# untitled.net
KiCad netlist of a schematic drawn in EAGLE
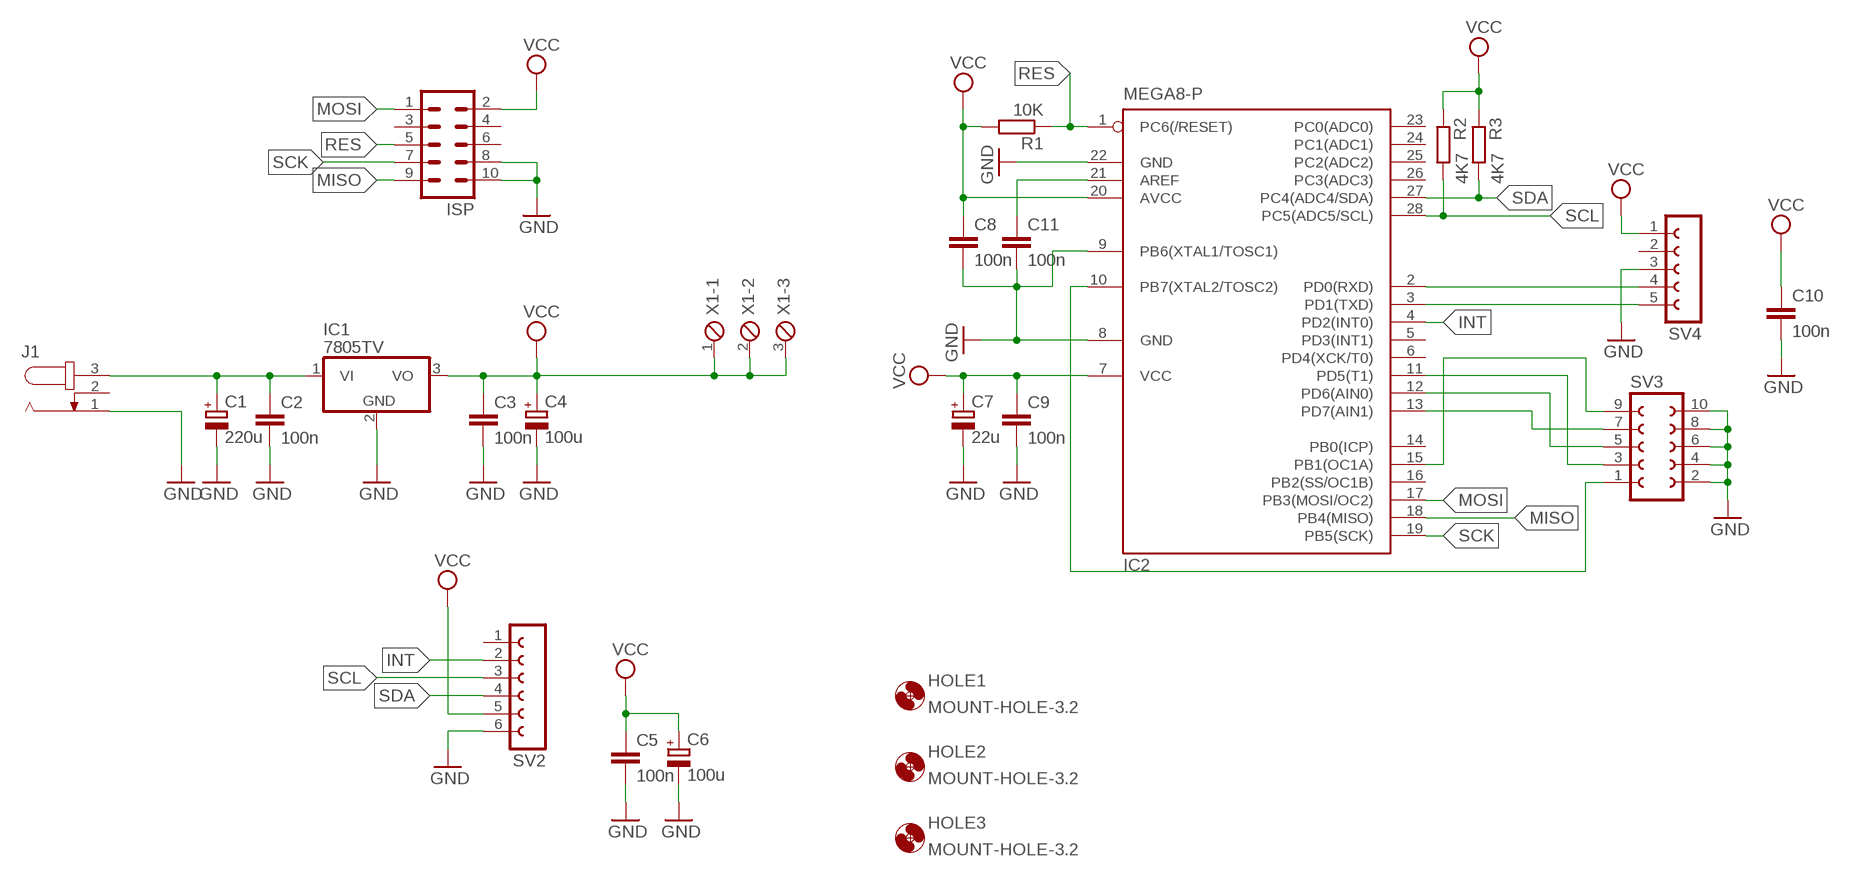
[diagram p0: schematic, sheet 1]

(export (version "E")
  (design (tool "Eeschema 10.0.6"))
  (components
    (comp (ref "C1")
      (value "220u")
      (footprint "eagle-import:E3,5-8")
      (libsource (lib "eagle-import") (part "CPOL-EUE3.5-8"))
    )
    (comp (ref "C2")
      (value "100n")
      (footprint "eagle-import:C025-025X050")
      (libsource (lib "eagle-import") (part "C-EU025-025X050"))
    )
    (comp (ref "C3")
      (value "100n")
      (footprint "eagle-import:C025-025X050")
      (libsource (lib "eagle-import") (part "C-EU025-025X050"))
    )
    (comp (ref "C4")
      (value "100u")
      (footprint "eagle-import:E2,5-5")
      (libsource (lib "eagle-import") (part "CPOL-EUE2.5-5"))
    )
    (comp (ref "C5")
      (value "100n")
      (footprint "eagle-import:C025-025X050")
      (libsource (lib "eagle-import") (part "C-EU025-025X050"))
    )
    (comp (ref "C6")
      (value "100u")
      (footprint "eagle-import:E2,5-5")
      (libsource (lib "eagle-import") (part "CPOL-EUE2.5-5"))
    )
    (comp (ref "C7")
      (value "22u")
      (footprint "eagle-import:E2,5-5")
      (libsource (lib "eagle-import") (part "CPOL-EUE2.5-5"))
    )
    (comp (ref "C8")
      (value "100n")
      (footprint "eagle-import:C025-025X050")
      (libsource (lib "eagle-import") (part "C-EU025-025X050"))
    )
    (comp (ref "C9")
      (value "100n")
      (footprint "eagle-import:C025-030X050")
      (libsource (lib "eagle-import") (part "C-EU025-030X050"))
    )
    (comp (ref "C10")
      (value "100n")
      (footprint "eagle-import:C025-025X050")
      (libsource (lib "eagle-import") (part "C-EU025-025X050"))
    )
    (comp (ref "C11")
      (value "100n")
      (footprint "eagle-import:C025-025X050")
      (libsource (lib "eagle-import") (part "C-EU025-025X050"))
    )
    (comp (ref "HOLE1")
      (value "MOUNT-HOLE-3.2")
      (footprint "eagle-import:3,2")
      (libsource (lib "eagle-import") (part "MOUNT-HOLE-3.2"))
    )
    (comp (ref "HOLE2")
      (value "MOUNT-HOLE-3.2")
      (footprint "eagle-import:3,2")
      (libsource (lib "eagle-import") (part "MOUNT-HOLE-3.2"))
    )
    (comp (ref "HOLE3")
      (value "MOUNT-HOLE-3.2")
      (footprint "eagle-import:3,2")
      (libsource (lib "eagle-import") (part "MOUNT-HOLE-3.2"))
    )
    (comp (ref "IC1")
      (value "7805TV")
      (footprint "eagle-import:TO220V")
      (libsource (lib "eagle-import") (part "78TV05"))
    )
    (comp (ref "IC2")
      (value "MEGA8-P")
      (footprint "eagle-import:DIL28-3")
      (libsource (lib "eagle-import") (part "MEGA8-P"))
    )
    (comp (ref "ISP")
      (value "ML10")
      (footprint "eagle-import:ML10")
      (libsource (lib "eagle-import") (part "ML10"))
    )
    (comp (ref "J1")
      (value "JACK-PLUG1")
      (footprint "eagle-import:SPC4078")
      (libsource (lib "eagle-import") (part "JACK-PLUG1"))
    )
    (comp (ref "R1")
      (value "10K")
      (footprint "eagle-import:0204_7")
      (libsource (lib "eagle-import") (part "R-EU_0204/7"))
    )
    (comp (ref "R2")
      (value "4K7")
      (footprint "eagle-import:0204_7")
      (libsource (lib "eagle-import") (part "R-EU_0204/7"))
    )
    (comp (ref "R3")
      (value "4K7")
      (footprint "eagle-import:0204_7")
      (libsource (lib "eagle-import") (part "R-EU_0204/7"))
    )
    (comp (ref "SV2")
      (value "FE06-1")
      (footprint "eagle-import:FE06")
      (libsource (lib "eagle-import") (part "FE06-1"))
    )
    (comp (ref "SV3")
      (value "FE05-2")
      (footprint "eagle-import:FE05-2")
      (libsource (lib "eagle-import") (part "FE05-2"))
    )
    (comp (ref "SV4")
      (value "FE05-1")
      (footprint "eagle-import:FE05-1")
      (libsource (lib "eagle-import") (part "FE05-1"))
    )
    (comp (ref "X1")
      (value "MPT3")
      (footprint "eagle-import:3POL254")
      (libsource (lib "eagle-import") (part "MPT3"))
    )
  )
  (nets
    (net (code "1") (name "GND") (class "Default")
      (node (ref "C1") (pin "-") (pinfunction "-_-") (pintype "passive"))
      (node (ref "C10") (pin "2") (pinfunction "2_2") (pintype "passive"))
      (node (ref "C11") (pin "2") (pinfunction "2_2") (pintype "passive"))
      (node (ref "C2") (pin "2") (pinfunction "2_2") (pintype "passive"))
      (node (ref "C3") (pin "2") (pinfunction "2_2") (pintype "passive"))
      (node (ref "C4") (pin "-") (pinfunction "-_-") (pintype "passive"))
      (node (ref "C5") (pin "2") (pinfunction "2_2") (pintype "passive"))
      (node (ref "C6") (pin "-") (pinfunction "-_-") (pintype "passive"))
      (node (ref "C7") (pin "-") (pinfunction "-_-") (pintype "passive"))
      (node (ref "C8") (pin "2") (pinfunction "2_2") (pintype "passive"))
      (node (ref "C9") (pin "2") (pinfunction "2_2") (pintype "passive"))
      (node (ref "IC1") (pin "2") (pinfunction "GND_2") (pintype "passive"))
      (node (ref "IC2") (pin "22") (pinfunction "GND_22") (pintype "power_in"))
      (node (ref "IC2") (pin "8") (pinfunction "GND_8") (pintype "power_in"))
      (node (ref "IC2") (pin "9") (pinfunction "PB6(XTAL1/TOSC1)_9") (pintype "bidirectional"))
      (node (ref "ISP") (pin "10") (pinfunction "10_10") (pintype "passive"))
      (node (ref "ISP") (pin "8") (pinfunction "8_8") (pintype "passive"))
      (node (ref "J1") (pin "1") (pinfunction "1_1") (pintype "passive"))
      (node (ref "SV2") (pin "6") (pinfunction "6_6") (pintype "passive"))
      (node (ref "SV3") (pin "10") (pinfunction "10_10") (pintype "passive"))
      (node (ref "SV3") (pin "2") (pinfunction "2_2") (pintype "passive"))
      (node (ref "SV3") (pin "4") (pinfunction "4_4") (pintype "passive"))
      (node (ref "SV3") (pin "6") (pinfunction "6_6") (pintype "passive"))
      (node (ref "SV3") (pin "8") (pinfunction "8_8") (pintype "passive"))
      (node (ref "SV4") (pin "3") (pinfunction "3_3") (pintype "passive"))
    )
    (net (code "2") (name "INT") (class "Default")
      (node (ref "IC2") (pin "4") (pinfunction "PD2(INT0)_4") (pintype "bidirectional"))
      (node (ref "SV2") (pin "2") (pinfunction "2_2") (pintype "passive"))
    )
    (net (code "3") (name "MISO") (class "Default")
      (node (ref "IC2") (pin "18") (pinfunction "PB4(MISO)_18") (pintype "bidirectional"))
      (node (ref "ISP") (pin "9") (pinfunction "9_9") (pintype "passive"))
    )
    (net (code "4") (name "MOSI") (class "Default")
      (node (ref "IC2") (pin "17") (pinfunction "PB3(MOSI/OC2)_17") (pintype "bidirectional"))
      (node (ref "ISP") (pin "1") (pinfunction "1_1") (pintype "passive"))
    )
    (net (code "5") (name "Net-(IC1-VI)") (class "Default")
      (node (ref "C1") (pin "+") (pinfunction "+_+") (pintype "passive"))
      (node (ref "C2") (pin "1") (pinfunction "1_1") (pintype "passive"))
      (node (ref "IC1") (pin "1") (pinfunction "VI_1") (pintype "input"))
      (node (ref "J1") (pin "3") (pinfunction "3_3") (pintype "passive"))
    )
    (net (code "6") (name "Net-(IC2-AREF)") (class "Default")
      (node (ref "C11") (pin "1") (pinfunction "1_1") (pintype "passive"))
      (node (ref "IC2") (pin "21") (pinfunction "AREF_21") (pintype "passive"))
    )
    (net (code "7") (name "Net-(IC2-PB1(OC1A))") (class "Default")
      (node (ref "IC2") (pin "15") (pinfunction "PB1(OC1A)_15") (pintype "bidirectional"))
      (node (ref "SV3") (pin "9") (pinfunction "9_9") (pintype "passive"))
    )
    (net (code "8") (name "Net-(IC2-PB7(XTAL2{slash}TOSC2))") (class "Default")
      (node (ref "IC2") (pin "10") (pinfunction "PB7(XTAL2/TOSC2)_10") (pintype "bidirectional"))
      (node (ref "SV3") (pin "1") (pinfunction "1_1") (pintype "passive"))
    )
    (net (code "9") (name "Net-(IC2-PD0(RXD))") (class "Default")
      (node (ref "IC2") (pin "2") (pinfunction "PD0(RXD)_2") (pintype "bidirectional"))
      (node (ref "SV4") (pin "4") (pinfunction "4_4") (pintype "passive"))
    )
    (net (code "10") (name "Net-(IC2-PD1(TXD))") (class "Default")
      (node (ref "IC2") (pin "3") (pinfunction "PD1(TXD)_3") (pintype "bidirectional"))
      (node (ref "SV4") (pin "5") (pinfunction "5_5") (pintype "passive"))
    )
    (net (code "11") (name "Net-(IC2-PD5(T1))") (class "Default")
      (node (ref "IC2") (pin "11") (pinfunction "PD5(T1)_11") (pintype "bidirectional"))
      (node (ref "SV3") (pin "3") (pinfunction "3_3") (pintype "passive"))
    )
    (net (code "12") (name "Net-(IC2-PD6(AIN0))") (class "Default")
      (node (ref "IC2") (pin "12") (pinfunction "PD6(AIN0)_12") (pintype "bidirectional"))
      (node (ref "SV3") (pin "5") (pinfunction "5_5") (pintype "passive"))
    )
    (net (code "13") (name "Net-(IC2-PD7(AIN1))") (class "Default")
      (node (ref "IC2") (pin "13") (pinfunction "PD7(AIN1)_13") (pintype "bidirectional"))
      (node (ref "SV3") (pin "7") (pinfunction "7_7") (pintype "passive"))
    )
    (net (code "14") (name "RES") (class "Default")
      (node (ref "IC2") (pin "1") (pinfunction "PC6(/RESET)_1") (pintype "bidirectional"))
      (node (ref "ISP") (pin "5") (pinfunction "5_5") (pintype "passive"))
      (node (ref "R1") (pin "1") (pinfunction "1_1") (pintype "passive"))
    )
    (net (code "15") (name "SCK") (class "Default")
      (node (ref "IC2") (pin "19") (pinfunction "PB5(SCK)_19") (pintype "bidirectional"))
      (node (ref "ISP") (pin "7") (pinfunction "7_7") (pintype "passive"))
    )
    (net (code "16") (name "SCL") (class "Default")
      (node (ref "IC2") (pin "28") (pinfunction "PC5(ADC5/SCL)_28") (pintype "bidirectional"))
      (node (ref "R2") (pin "2") (pinfunction "2_2") (pintype "passive"))
      (node (ref "SV2") (pin "3") (pinfunction "3_3") (pintype "passive"))
    )
    (net (code "17") (name "SDA") (class "Default")
      (node (ref "IC2") (pin "27") (pinfunction "PC4(ADC4/SDA)_27") (pintype "bidirectional"))
      (node (ref "R3") (pin "2") (pinfunction "2_2") (pintype "passive"))
      (node (ref "SV2") (pin "4") (pinfunction "4_4") (pintype "passive"))
    )
    (net (code "18") (name "VCC") (class "Default")
      (node (ref "C10") (pin "1") (pinfunction "1_1") (pintype "passive"))
      (node (ref "C3") (pin "1") (pinfunction "1_1") (pintype "passive"))
      (node (ref "C4") (pin "+") (pinfunction "+_+") (pintype "passive"))
      (node (ref "C5") (pin "1") (pinfunction "1_1") (pintype "passive"))
      (node (ref "C6") (pin "+") (pinfunction "+_+") (pintype "passive"))
      (node (ref "C7") (pin "+") (pinfunction "+_+") (pintype "passive"))
      (node (ref "C8") (pin "1") (pinfunction "1_1") (pintype "passive"))
      (node (ref "C9") (pin "1") (pinfunction "1_1") (pintype "passive"))
      (node (ref "IC1") (pin "3") (pinfunction "VO_3") (pintype "passive"))
      (node (ref "IC2") (pin "20") (pinfunction "AVCC_20") (pintype "power_in"))
      (node (ref "IC2") (pin "7") (pinfunction "VCC_7") (pintype "power_in"))
      (node (ref "ISP") (pin "2") (pinfunction "2_2") (pintype "passive"))
      (node (ref "R1") (pin "2") (pinfunction "2_2") (pintype "passive"))
      (node (ref "R2") (pin "1") (pinfunction "1_1") (pintype "passive"))
      (node (ref "R3") (pin "1") (pinfunction "1_1") (pintype "passive"))
      (node (ref "SV2") (pin "5") (pinfunction "5_5") (pintype "passive"))
      (node (ref "SV4") (pin "1") (pinfunction "1_1") (pintype "passive"))
      (node (ref "X1") (pin "1") (pinfunction "1_1") (pintype "passive"))
      (node (ref "X1") (pin "2") (pinfunction "1_2") (pintype "passive"))
      (node (ref "X1") (pin "3") (pinfunction "1_3") (pintype "passive"))
    )
    (net (code "19") (name "unconnected-(IC2-PB0(ICP)-Pad14)") (class "Default")
      (node (ref "IC2") (pin "14") (pinfunction "PB0(ICP)_14") (pintype "bidirectional"))
    )
    (net (code "20") (name "unconnected-(IC2-PB2(SS{slash}OC1B)-Pad16)") (class "Default")
      (node (ref "IC2") (pin "16") (pinfunction "PB2(SS/OC1B)_16") (pintype "bidirectional"))
    )
    (net (code "21") (name "unconnected-(IC2-PC0(ADC0)-Pad23)") (class "Default")
      (node (ref "IC2") (pin "23") (pinfunction "PC0(ADC0)_23") (pintype "bidirectional"))
    )
    (net (code "22") (name "unconnected-(IC2-PC1(ADC1)-Pad24)") (class "Default")
      (node (ref "IC2") (pin "24") (pinfunction "PC1(ADC1)_24") (pintype "bidirectional"))
    )
    (net (code "23") (name "unconnected-(IC2-PC2(ADC2)-Pad25)") (class "Default")
      (node (ref "IC2") (pin "25") (pinfunction "PC2(ADC2)_25") (pintype "bidirectional"))
    )
    (net (code "24") (name "unconnected-(IC2-PC3(ADC3)-Pad26)") (class "Default")
      (node (ref "IC2") (pin "26") (pinfunction "PC3(ADC3)_26") (pintype "bidirectional"))
    )
    (net (code "25") (name "unconnected-(IC2-PD3(INT1)-Pad5)") (class "Default")
      (node (ref "IC2") (pin "5") (pinfunction "PD3(INT1)_5") (pintype "bidirectional"))
    )
    (net (code "26") (name "unconnected-(IC2-PD4(XCK{slash}T0)-Pad6)") (class "Default")
      (node (ref "IC2") (pin "6") (pinfunction "PD4(XCK/T0)_6") (pintype "bidirectional"))
    )
    (net (code "27") (name "unconnected-(ISP-Pad3)") (class "Default")
      (node (ref "ISP") (pin "3") (pinfunction "3_3") (pintype "passive"))
    )
    (net (code "28") (name "unconnected-(ISP-Pad4)") (class "Default")
      (node (ref "ISP") (pin "4") (pinfunction "4_4") (pintype "passive"))
    )
    (net (code "29") (name "unconnected-(ISP-Pad6)") (class "Default")
      (node (ref "ISP") (pin "6") (pinfunction "6_6") (pintype "passive"))
    )
    (net (code "30") (name "unconnected-(J1-Pad2)") (class "Default")
      (node (ref "J1") (pin "2") (pinfunction "2_2") (pintype "passive"))
    )
    (net (code "31") (name "unconnected-(SV2-Pad1)") (class "Default")
      (node (ref "SV2") (pin "1") (pinfunction "1_1") (pintype "passive"))
    )
    (net (code "32") (name "unconnected-(SV4-Pad2)") (class "Default")
      (node (ref "SV4") (pin "2") (pinfunction "2_2") (pintype "passive"))
    )
  )
)
